# schema_mpb1_1_IO.net
KiCad netlist of a schematic drawn in EAGLE
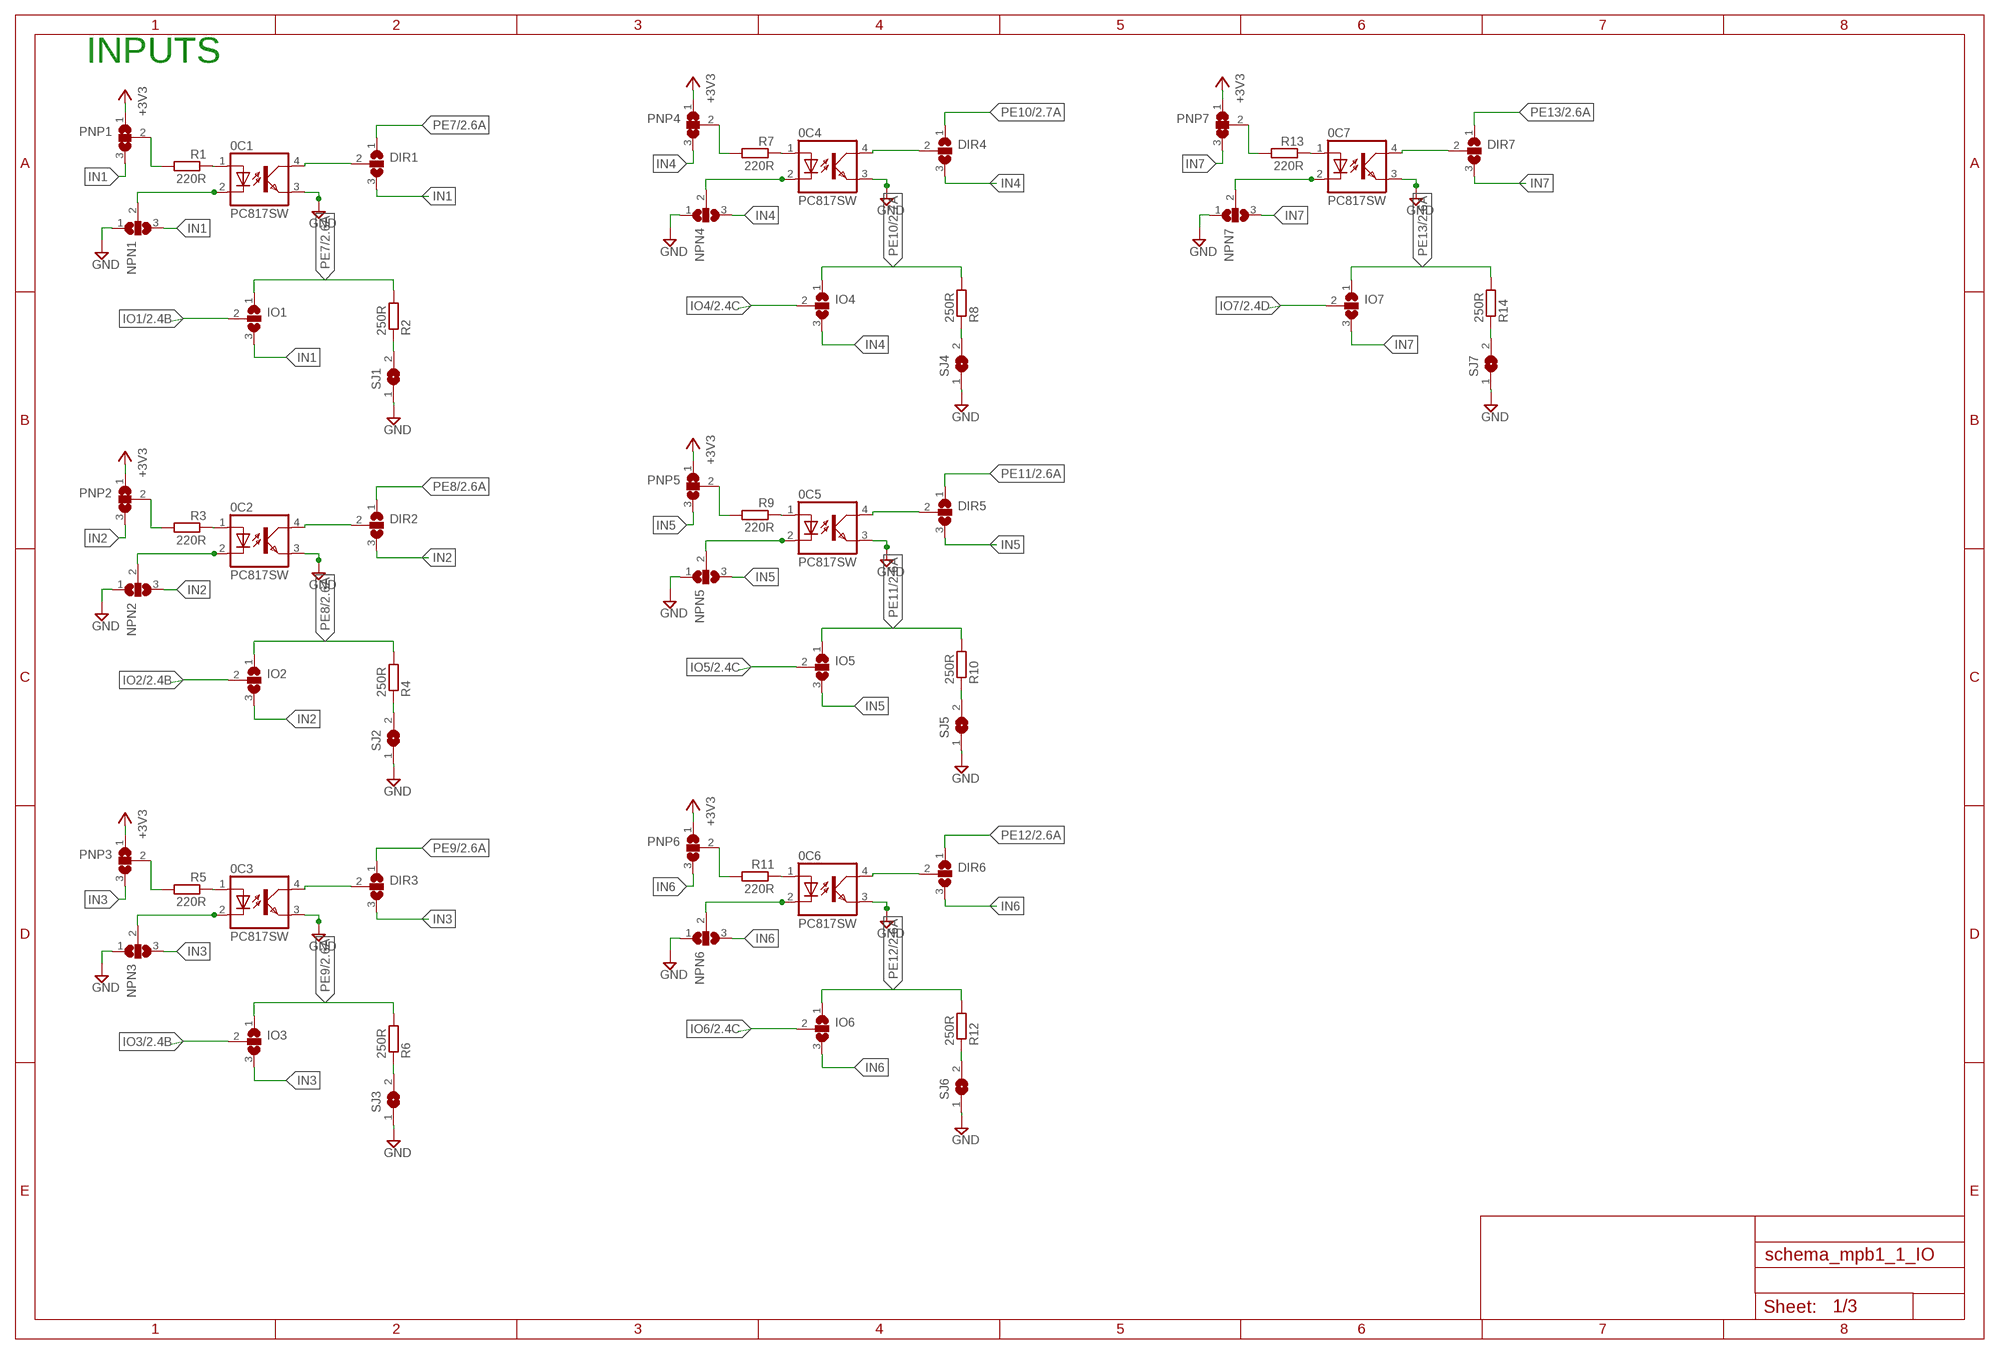
[diagram p0: schematic, sheet 1]
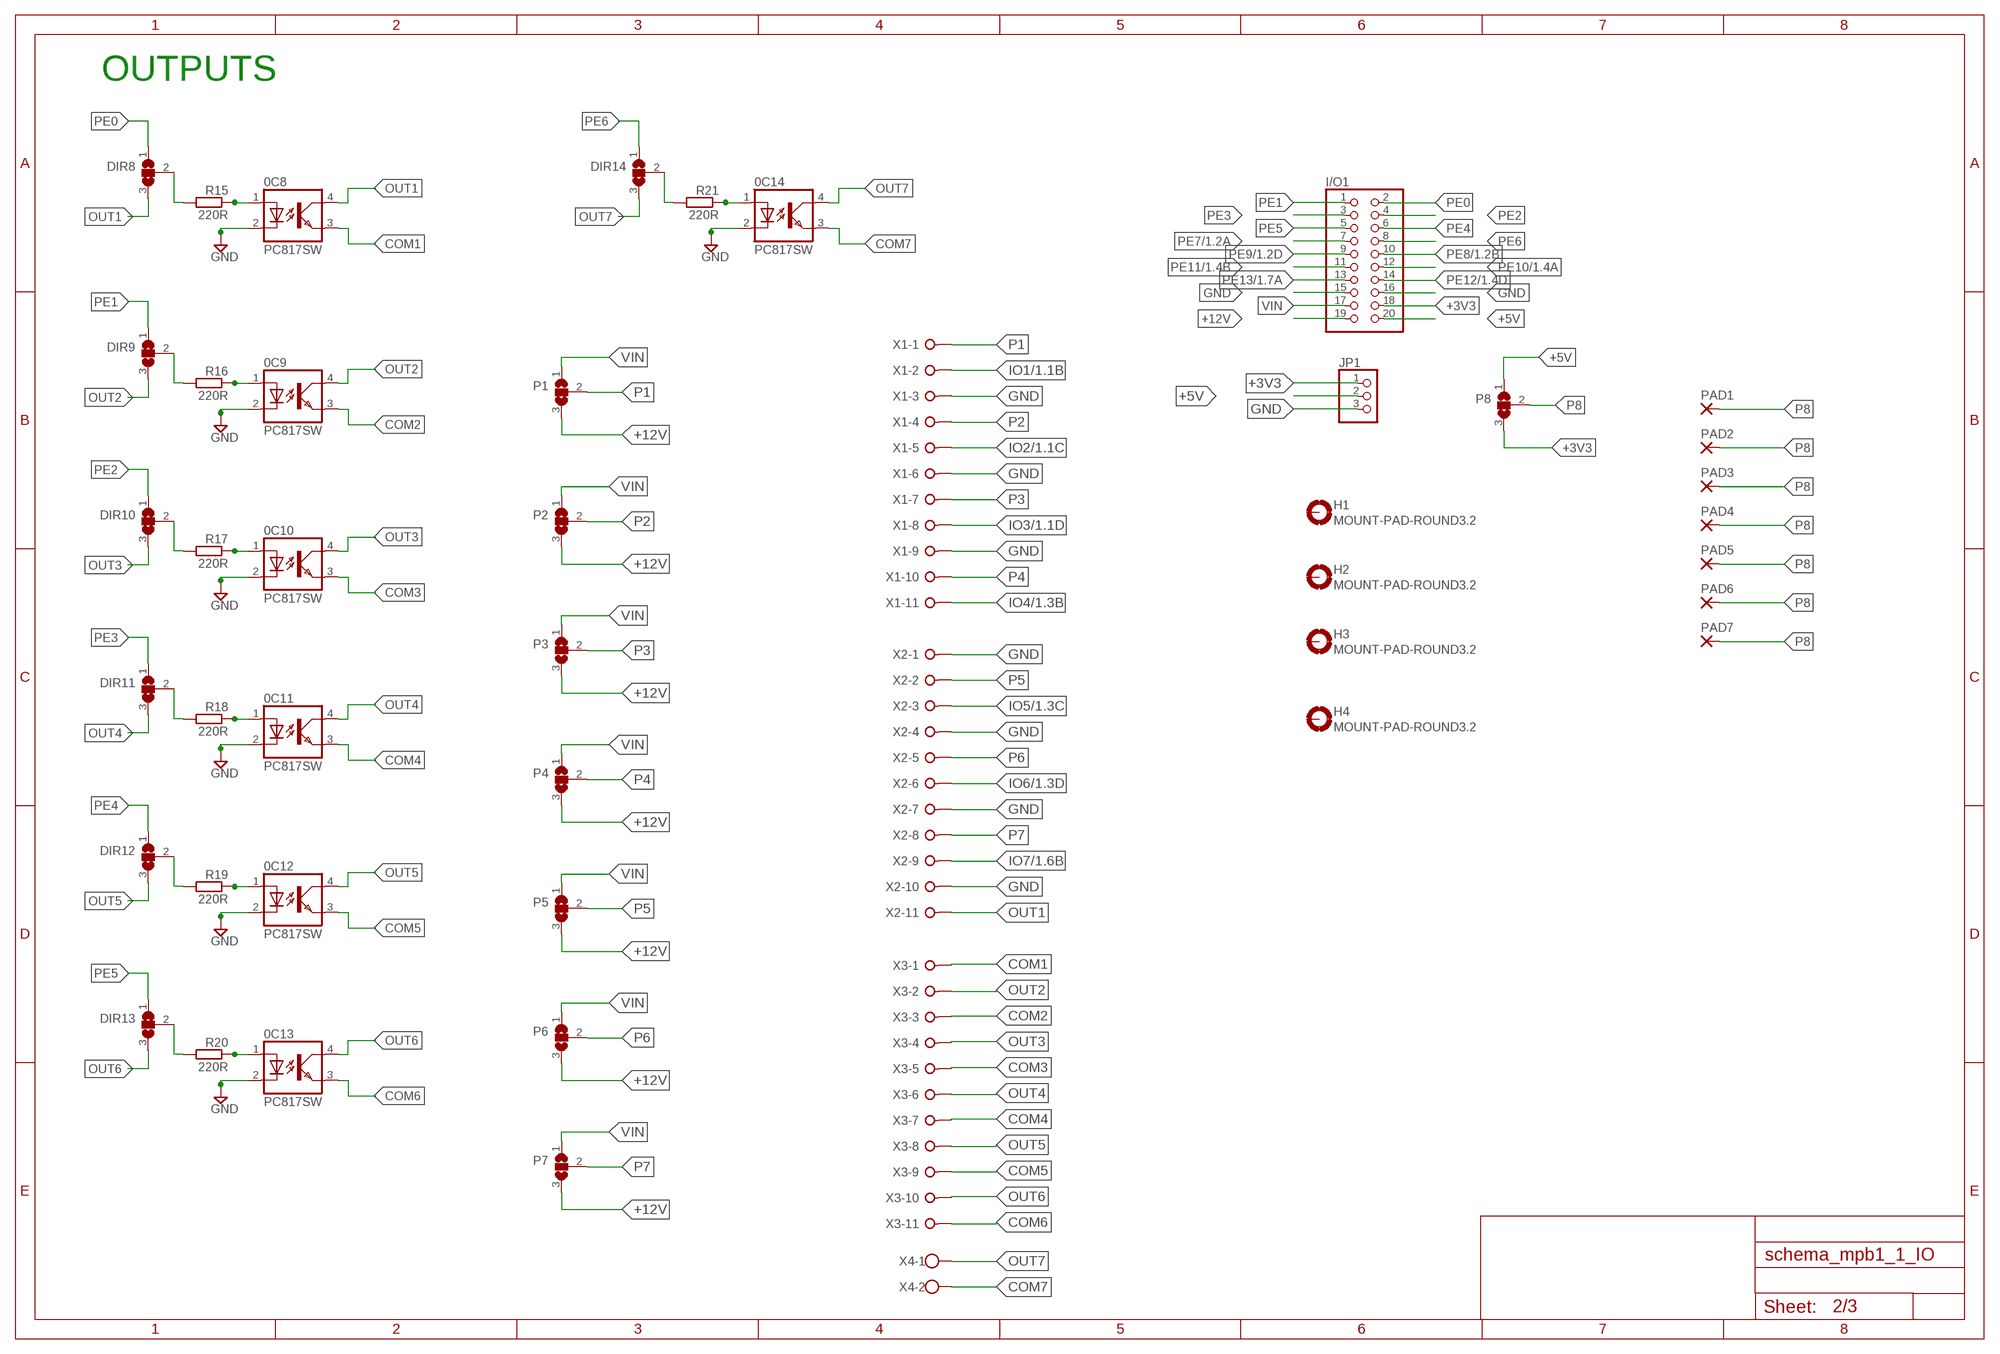
[diagram p1: schematic, sheet 2]

(export (version "E")
  (design (tool "Eeschema 10.0.6"))
  (components
    (comp (ref "0C1")
      (value "PC817SW")
      (footprint "eagle-import:PC817SMTW")
      (libsource (lib "eagle-import") (part "PC817SW"))
    )
    (comp (ref "0C2")
      (value "PC817SW")
      (footprint "eagle-import:PC817SMTW")
      (libsource (lib "eagle-import") (part "PC817SW"))
    )
    (comp (ref "0C3")
      (value "PC817SW")
      (footprint "eagle-import:PC817SMTW")
      (libsource (lib "eagle-import") (part "PC817SW"))
    )
    (comp (ref "0C4")
      (value "PC817SW")
      (footprint "eagle-import:PC817SMTW")
      (libsource (lib "eagle-import") (part "PC817SW"))
    )
    (comp (ref "0C5")
      (value "PC817SW")
      (footprint "eagle-import:PC817SMTW")
      (libsource (lib "eagle-import") (part "PC817SW"))
    )
    (comp (ref "0C6")
      (value "PC817SW")
      (footprint "eagle-import:PC817SMTW")
      (libsource (lib "eagle-import") (part "PC817SW"))
    )
    (comp (ref "0C7")
      (value "PC817SW")
      (footprint "eagle-import:PC817SMTW")
      (libsource (lib "eagle-import") (part "PC817SW"))
    )
    (comp (ref "DIR1")
      (value "SJ2W")
      (footprint "eagle-import:SJ_2")
      (libsource (lib "eagle-import") (part "SJ2W"))
    )
    (comp (ref "DIR2")
      (value "SJ2W")
      (footprint "eagle-import:SJ_2")
      (libsource (lib "eagle-import") (part "SJ2W"))
    )
    (comp (ref "DIR3")
      (value "SJ2W")
      (footprint "eagle-import:SJ_2")
      (libsource (lib "eagle-import") (part "SJ2W"))
    )
    (comp (ref "DIR4")
      (value "SJ2W")
      (footprint "eagle-import:SJ_2")
      (libsource (lib "eagle-import") (part "SJ2W"))
    )
    (comp (ref "DIR5")
      (value "SJ2W")
      (footprint "eagle-import:SJ_2")
      (libsource (lib "eagle-import") (part "SJ2W"))
    )
    (comp (ref "DIR6")
      (value "SJ2W")
      (footprint "eagle-import:SJ_2")
      (libsource (lib "eagle-import") (part "SJ2W"))
    )
    (comp (ref "DIR7")
      (value "SJ2W")
      (footprint "eagle-import:SJ_2")
      (libsource (lib "eagle-import") (part "SJ2W"))
    )
    (comp (ref "IO1")
      (value "SJ2W")
      (footprint "eagle-import:SJ_2")
      (libsource (lib "eagle-import") (part "SJ2W"))
    )
    (comp (ref "IO2")
      (value "SJ2W")
      (footprint "eagle-import:SJ_2")
      (libsource (lib "eagle-import") (part "SJ2W"))
    )
    (comp (ref "IO3")
      (value "SJ2W")
      (footprint "eagle-import:SJ_2")
      (libsource (lib "eagle-import") (part "SJ2W"))
    )
    (comp (ref "IO4")
      (value "SJ2W")
      (footprint "eagle-import:SJ_2")
      (libsource (lib "eagle-import") (part "SJ2W"))
    )
    (comp (ref "IO5")
      (value "SJ2W")
      (footprint "eagle-import:SJ_2")
      (libsource (lib "eagle-import") (part "SJ2W"))
    )
    (comp (ref "IO6")
      (value "SJ2W")
      (footprint "eagle-import:SJ_2")
      (libsource (lib "eagle-import") (part "SJ2W"))
    )
    (comp (ref "IO7")
      (value "SJ2W")
      (footprint "eagle-import:SJ_2")
      (libsource (lib "eagle-import") (part "SJ2W"))
    )
    (comp (ref "NPN1")
      (value "SJ2W")
      (footprint "eagle-import:SJ_2")
      (libsource (lib "eagle-import") (part "SJ2W"))
    )
    (comp (ref "NPN2")
      (value "SJ2W")
      (footprint "eagle-import:SJ_2")
      (libsource (lib "eagle-import") (part "SJ2W"))
    )
    (comp (ref "NPN3")
      (value "SJ2W")
      (footprint "eagle-import:SJ_2")
      (libsource (lib "eagle-import") (part "SJ2W"))
    )
    (comp (ref "NPN4")
      (value "SJ2W")
      (footprint "eagle-import:SJ_2")
      (libsource (lib "eagle-import") (part "SJ2W"))
    )
    (comp (ref "NPN5")
      (value "SJ2W")
      (footprint "eagle-import:SJ_2")
      (libsource (lib "eagle-import") (part "SJ2W"))
    )
    (comp (ref "NPN6")
      (value "SJ2W")
      (footprint "eagle-import:SJ_2")
      (libsource (lib "eagle-import") (part "SJ2W"))
    )
    (comp (ref "NPN7")
      (value "SJ2W")
      (footprint "eagle-import:SJ_2")
      (libsource (lib "eagle-import") (part "SJ2W"))
    )
    (comp (ref "PNP1")
      (value "SJ2W")
      (footprint "eagle-import:SJ_2")
      (libsource (lib "eagle-import") (part "SJ2W"))
    )
    (comp (ref "PNP2")
      (value "SJ2W")
      (footprint "eagle-import:SJ_2")
      (libsource (lib "eagle-import") (part "SJ2W"))
    )
    (comp (ref "PNP3")
      (value "SJ2W")
      (footprint "eagle-import:SJ_2")
      (libsource (lib "eagle-import") (part "SJ2W"))
    )
    (comp (ref "PNP4")
      (value "SJ2W")
      (footprint "eagle-import:SJ_2")
      (libsource (lib "eagle-import") (part "SJ2W"))
    )
    (comp (ref "PNP5")
      (value "SJ2W")
      (footprint "eagle-import:SJ_2")
      (libsource (lib "eagle-import") (part "SJ2W"))
    )
    (comp (ref "PNP6")
      (value "SJ2W")
      (footprint "eagle-import:SJ_2")
      (libsource (lib "eagle-import") (part "SJ2W"))
    )
    (comp (ref "PNP7")
      (value "SJ2W")
      (footprint "eagle-import:SJ_2")
      (libsource (lib "eagle-import") (part "SJ2W"))
    )
    (comp (ref "R1")
      (value "220R")
      (footprint "eagle-import:R0603")
      (libsource (lib "eagle-import") (part "R-EU_R0603"))
    )
    (comp (ref "R2")
      (value "250R")
      (footprint "eagle-import:R0603")
      (libsource (lib "eagle-import") (part "R-EU_R0603"))
    )
    (comp (ref "R3")
      (value "220R")
      (footprint "eagle-import:R0603")
      (libsource (lib "eagle-import") (part "R-EU_R0603"))
    )
    (comp (ref "R4")
      (value "250R")
      (footprint "eagle-import:R0603")
      (libsource (lib "eagle-import") (part "R-EU_R0603"))
    )
    (comp (ref "R5")
      (value "220R")
      (footprint "eagle-import:R0603")
      (libsource (lib "eagle-import") (part "R-EU_R0603"))
    )
    (comp (ref "R6")
      (value "250R")
      (footprint "eagle-import:R0603")
      (libsource (lib "eagle-import") (part "R-EU_R0603"))
    )
    (comp (ref "R7")
      (value "220R")
      (footprint "eagle-import:R0603")
      (libsource (lib "eagle-import") (part "R-EU_R0603"))
    )
    (comp (ref "R8")
      (value "250R")
      (footprint "eagle-import:R0603")
      (libsource (lib "eagle-import") (part "R-EU_R0603"))
    )
    (comp (ref "R9")
      (value "220R")
      (footprint "eagle-import:R0603")
      (libsource (lib "eagle-import") (part "R-EU_R0603"))
    )
    (comp (ref "R10")
      (value "250R")
      (footprint "eagle-import:R0603")
      (libsource (lib "eagle-import") (part "R-EU_R0603"))
    )
    (comp (ref "R11")
      (value "220R")
      (footprint "eagle-import:R0603")
      (libsource (lib "eagle-import") (part "R-EU_R0603"))
    )
    (comp (ref "R12")
      (value "250R")
      (footprint "eagle-import:R0603")
      (libsource (lib "eagle-import") (part "R-EU_R0603"))
    )
    (comp (ref "R13")
      (value "220R")
      (footprint "eagle-import:R0603")
      (libsource (lib "eagle-import") (part "R-EU_R0603"))
    )
    (comp (ref "R14")
      (value "250R")
      (footprint "eagle-import:R0603")
      (libsource (lib "eagle-import") (part "R-EU_R0603"))
    )
    (comp (ref "SJ1") (value "SJ") (footprint "eagle-import:SJ") (libsource (lib "eagle-import") (part "SJ")))
    (comp (ref "SJ2") (value "SJ") (footprint "eagle-import:SJ") (libsource (lib "eagle-import") (part "SJ")))
    (comp (ref "SJ3") (value "SJ") (footprint "eagle-import:SJ") (libsource (lib "eagle-import") (part "SJ")))
    (comp (ref "SJ4") (value "SJ") (footprint "eagle-import:SJ") (libsource (lib "eagle-import") (part "SJ")))
    (comp (ref "SJ5") (value "SJ") (footprint "eagle-import:SJ") (libsource (lib "eagle-import") (part "SJ")))
    (comp (ref "SJ6") (value "SJ") (footprint "eagle-import:SJ") (libsource (lib "eagle-import") (part "SJ")))
    (comp (ref "SJ7") (value "SJ") (footprint "eagle-import:SJ") (libsource (lib "eagle-import") (part "SJ")))
    (comp (ref "0C8")
      (value "PC817SW")
      (footprint "eagle-import:PC817SMTW")
      (libsource (lib "eagle-import") (part "PC817SW"))
    )
    (comp (ref "0C9")
      (value "PC817SW")
      (footprint "eagle-import:PC817SMTW")
      (libsource (lib "eagle-import") (part "PC817SW"))
    )
    (comp (ref "0C10")
      (value "PC817SW")
      (footprint "eagle-import:PC817SMTW")
      (libsource (lib "eagle-import") (part "PC817SW"))
    )
    (comp (ref "0C11")
      (value "PC817SW")
      (footprint "eagle-import:PC817SMTW")
      (libsource (lib "eagle-import") (part "PC817SW"))
    )
    (comp (ref "0C12")
      (value "PC817SW")
      (footprint "eagle-import:PC817SMTW")
      (libsource (lib "eagle-import") (part "PC817SW"))
    )
    (comp (ref "0C13")
      (value "PC817SW")
      (footprint "eagle-import:PC817SMTW")
      (libsource (lib "eagle-import") (part "PC817SW"))
    )
    (comp (ref "0C14")
      (value "PC817SW")
      (footprint "eagle-import:PC817SMTW")
      (libsource (lib "eagle-import") (part "PC817SW"))
    )
    (comp (ref "DIR8")
      (value "SJ2W")
      (footprint "eagle-import:SJ_2")
      (libsource (lib "eagle-import") (part "SJ2W"))
    )
    (comp (ref "DIR9")
      (value "SJ2W")
      (footprint "eagle-import:SJ_2")
      (libsource (lib "eagle-import") (part "SJ2W"))
    )
    (comp (ref "DIR10")
      (value "SJ2W")
      (footprint "eagle-import:SJ_2")
      (libsource (lib "eagle-import") (part "SJ2W"))
    )
    (comp (ref "DIR11")
      (value "SJ2W")
      (footprint "eagle-import:SJ_2")
      (libsource (lib "eagle-import") (part "SJ2W"))
    )
    (comp (ref "DIR12")
      (value "SJ2W")
      (footprint "eagle-import:SJ_2")
      (libsource (lib "eagle-import") (part "SJ2W"))
    )
    (comp (ref "DIR13")
      (value "SJ2W")
      (footprint "eagle-import:SJ_2")
      (libsource (lib "eagle-import") (part "SJ2W"))
    )
    (comp (ref "DIR14")
      (value "SJ2W")
      (footprint "eagle-import:SJ_2")
      (libsource (lib "eagle-import") (part "SJ2W"))
    )
    (comp (ref "H1")
      (value "MOUNT-PAD-ROUND3.2")
      (footprint "eagle-import:3,2-PAD")
      (libsource (lib "eagle-import") (part "MOUNT-PAD-ROUND3.2"))
    )
    (comp (ref "H2")
      (value "MOUNT-PAD-ROUND3.2")
      (footprint "eagle-import:3,2-PAD")
      (libsource (lib "eagle-import") (part "MOUNT-PAD-ROUND3.2"))
    )
    (comp (ref "H3")
      (value "MOUNT-PAD-ROUND3.2")
      (footprint "eagle-import:3,2-PAD")
      (libsource (lib "eagle-import") (part "MOUNT-PAD-ROUND3.2"))
    )
    (comp (ref "H4")
      (value "MOUNT-PAD-ROUND3.2")
      (footprint "eagle-import:3,2-PAD")
      (libsource (lib "eagle-import") (part "MOUNT-PAD-ROUND3.2"))
    )
    (comp (ref "I/O1")
      (value "PINHD-2X10_2.54")
      (footprint "eagle-import:2X10")
      (libsource (lib "eagle-import") (part "PINHD-2X10_2.54"))
    )
    (comp (ref "JP1")
      (value "PINHD-1X3")
      (footprint "eagle-import:1X03")
      (libsource (lib "eagle-import") (part "PINHD-1X3"))
    )
    (comp (ref "P1")
      (value "SJ2WW")
      (footprint "eagle-import:SJ_2W")
      (libsource (lib "eagle-import") (part "SJ2WW"))
    )
    (comp (ref "P2")
      (value "SJ2WW")
      (footprint "eagle-import:SJ_2W")
      (libsource (lib "eagle-import") (part "SJ2WW"))
    )
    (comp (ref "P3")
      (value "SJ2WW")
      (footprint "eagle-import:SJ_2W")
      (libsource (lib "eagle-import") (part "SJ2WW"))
    )
    (comp (ref "P4")
      (value "SJ2WW")
      (footprint "eagle-import:SJ_2W")
      (libsource (lib "eagle-import") (part "SJ2WW"))
    )
    (comp (ref "P5")
      (value "SJ2WW")
      (footprint "eagle-import:SJ_2W")
      (libsource (lib "eagle-import") (part "SJ2WW"))
    )
    (comp (ref "P6")
      (value "SJ2WW")
      (footprint "eagle-import:SJ_2W")
      (libsource (lib "eagle-import") (part "SJ2WW"))
    )
    (comp (ref "P7")
      (value "SJ2WW")
      (footprint "eagle-import:SJ_2W")
      (libsource (lib "eagle-import") (part "SJ2WW"))
    )
    (comp (ref "P8")
      (value "SJ2WW")
      (footprint "eagle-import:SJ_2W")
      (libsource (lib "eagle-import") (part "SJ2WW"))
    )
    (comp (ref "PAD1")
      (value "SMD2")
      (footprint "eagle-import:SMD1,27-2,54")
      (libsource (lib "eagle-import") (part "SMD2"))
    )
    (comp (ref "PAD2")
      (value "SMD2")
      (footprint "eagle-import:SMD1,27-2,54")
      (libsource (lib "eagle-import") (part "SMD2"))
    )
    (comp (ref "PAD3")
      (value "SMD2")
      (footprint "eagle-import:SMD1,27-2,54")
      (libsource (lib "eagle-import") (part "SMD2"))
    )
    (comp (ref "PAD4")
      (value "SMD2")
      (footprint "eagle-import:SMD1,27-2,54")
      (libsource (lib "eagle-import") (part "SMD2"))
    )
    (comp (ref "PAD5")
      (value "SMD2")
      (footprint "eagle-import:SMD1,27-2,54")
      (libsource (lib "eagle-import") (part "SMD2"))
    )
    (comp (ref "PAD6")
      (value "SMD2")
      (footprint "eagle-import:SMD1,27-2,54")
      (libsource (lib "eagle-import") (part "SMD2"))
    )
    (comp (ref "PAD7")
      (value "SMD2")
      (footprint "eagle-import:SMD1,27-2,54")
      (libsource (lib "eagle-import") (part "SMD2"))
    )
    (comp (ref "R15")
      (value "220R")
      (footprint "eagle-import:R0603")
      (libsource (lib "eagle-import") (part "R-EU_R0603"))
    )
    (comp (ref "R16")
      (value "220R")
      (footprint "eagle-import:R0603")
      (libsource (lib "eagle-import") (part "R-EU_R0603"))
    )
    (comp (ref "R17")
      (value "220R")
      (footprint "eagle-import:R0603")
      (libsource (lib "eagle-import") (part "R-EU_R0603"))
    )
    (comp (ref "R18")
      (value "220R")
      (footprint "eagle-import:R0603")
      (libsource (lib "eagle-import") (part "R-EU_R0603"))
    )
    (comp (ref "R19")
      (value "220R")
      (footprint "eagle-import:R0603")
      (libsource (lib "eagle-import") (part "R-EU_R0603"))
    )
    (comp (ref "R20")
      (value "220R")
      (footprint "eagle-import:R0603")
      (libsource (lib "eagle-import") (part "R-EU_R0603"))
    )
    (comp (ref "R21")
      (value "220R")
      (footprint "eagle-import:R0603")
      (libsource (lib "eagle-import") (part "R-EU_R0603"))
    )
    (comp (ref "X1")
      (value "W237-11P")
      (footprint "eagle-import:W237-11P")
      (libsource (lib "eagle-import") (part "W237-11P"))
    )
    (comp (ref "X2")
      (value "W237-11P")
      (footprint "eagle-import:W237-11P")
      (libsource (lib "eagle-import") (part "W237-11P"))
    )
    (comp (ref "X3")
      (value "W237-11P")
      (footprint "eagle-import:W237-11P")
      (libsource (lib "eagle-import") (part "W237-11P"))
    )
    (comp (ref "X4")
      (value "W237-102")
      (footprint "eagle-import:W237-102")
      (fields (field (name "MPN") "237-102"))
      (libsource (lib "eagle-import") (part "W237-102"))
    )
  )
  (nets
    (net (code "1") (name "+3V3") (class "Default")
      (node (ref "I/O1") (pin "18") (pinfunction "18_18") (pintype "passive"))
      (node (ref "JP1") (pin "1") (pinfunction "1_1") (pintype "passive"))
      (node (ref "P8") (pin "3") (pinfunction "3_3") (pintype "passive"))
      (node (ref "PNP1") (pin "1") (pinfunction "1_1") (pintype "passive"))
      (node (ref "PNP2") (pin "1") (pinfunction "1_1") (pintype "passive"))
      (node (ref "PNP3") (pin "1") (pinfunction "1_1") (pintype "passive"))
      (node (ref "PNP4") (pin "1") (pinfunction "1_1") (pintype "passive"))
      (node (ref "PNP5") (pin "1") (pinfunction "1_1") (pintype "passive"))
      (node (ref "PNP6") (pin "1") (pinfunction "1_1") (pintype "passive"))
      (node (ref "PNP7") (pin "1") (pinfunction "1_1") (pintype "passive"))
    )
    (net (code "2") (name "+5V") (class "Default")
      (node (ref "I/O1") (pin "20") (pinfunction "20_20") (pintype "passive"))
      (node (ref "JP1") (pin "2") (pinfunction "2_2") (pintype "passive"))
      (node (ref "P8") (pin "1") (pinfunction "1_1") (pintype "passive"))
    )
    (net (code "3") (name "+12V") (class "Default")
      (node (ref "I/O1") (pin "19") (pinfunction "19_19") (pintype "passive"))
      (node (ref "P1") (pin "3") (pinfunction "3_3") (pintype "passive"))
      (node (ref "P2") (pin "3") (pinfunction "3_3") (pintype "passive"))
      (node (ref "P3") (pin "3") (pinfunction "3_3") (pintype "passive"))
      (node (ref "P4") (pin "3") (pinfunction "3_3") (pintype "passive"))
      (node (ref "P5") (pin "3") (pinfunction "3_3") (pintype "passive"))
      (node (ref "P6") (pin "3") (pinfunction "3_3") (pintype "passive"))
      (node (ref "P7") (pin "3") (pinfunction "3_3") (pintype "passive"))
    )
    (net (code "4") (name "COM1") (class "Default")
      (node (ref "0C8") (pin "3") (pinfunction "EMIT_3") (pintype "passive"))
      (node (ref "X3") (pin "1") (pinfunction "KL_1") (pintype "passive"))
    )
    (net (code "5") (name "COM2") (class "Default")
      (node (ref "0C9") (pin "3") (pinfunction "EMIT_3") (pintype "passive"))
      (node (ref "X3") (pin "3") (pinfunction "KL_3") (pintype "passive"))
    )
    (net (code "6") (name "COM3") (class "Default")
      (node (ref "0C10") (pin "3") (pinfunction "EMIT_3") (pintype "passive"))
      (node (ref "X3") (pin "5") (pinfunction "KL_5") (pintype "passive"))
    )
    (net (code "7") (name "COM4") (class "Default")
      (node (ref "0C11") (pin "3") (pinfunction "EMIT_3") (pintype "passive"))
      (node (ref "X3") (pin "7") (pinfunction "KL_7") (pintype "passive"))
    )
    (net (code "8") (name "COM5") (class "Default")
      (node (ref "0C12") (pin "3") (pinfunction "EMIT_3") (pintype "passive"))
      (node (ref "X3") (pin "9") (pinfunction "KL_9") (pintype "passive"))
    )
    (net (code "9") (name "COM6") (class "Default")
      (node (ref "0C13") (pin "3") (pinfunction "EMIT_3") (pintype "passive"))
      (node (ref "X3") (pin "11") (pinfunction "KL_11") (pintype "passive"))
    )
    (net (code "10") (name "COM7") (class "Default")
      (node (ref "0C14") (pin "3") (pinfunction "EMIT_3") (pintype "passive"))
      (node (ref "X4") (pin "2") (pinfunction "KL_2") (pintype "passive"))
    )
    (net (code "11") (name "GND") (class "Default")
      (node (ref "0C1") (pin "3") (pinfunction "EMIT_3") (pintype "passive"))
      (node (ref "0C10") (pin "2") (pinfunction "C_2") (pintype "passive"))
      (node (ref "0C11") (pin "2") (pinfunction "C_2") (pintype "passive"))
      (node (ref "0C12") (pin "2") (pinfunction "C_2") (pintype "passive"))
      (node (ref "0C13") (pin "2") (pinfunction "C_2") (pintype "passive"))
      (node (ref "0C14") (pin "2") (pinfunction "C_2") (pintype "passive"))
      (node (ref "0C2") (pin "3") (pinfunction "EMIT_3") (pintype "passive"))
      (node (ref "0C3") (pin "3") (pinfunction "EMIT_3") (pintype "passive"))
      (node (ref "0C4") (pin "3") (pinfunction "EMIT_3") (pintype "passive"))
      (node (ref "0C5") (pin "3") (pinfunction "EMIT_3") (pintype "passive"))
      (node (ref "0C6") (pin "3") (pinfunction "EMIT_3") (pintype "passive"))
      (node (ref "0C7") (pin "3") (pinfunction "EMIT_3") (pintype "passive"))
      (node (ref "0C8") (pin "2") (pinfunction "C_2") (pintype "passive"))
      (node (ref "0C9") (pin "2") (pinfunction "C_2") (pintype "passive"))
      (node (ref "I/O1") (pin "15") (pinfunction "15_15") (pintype "passive"))
      (node (ref "I/O1") (pin "16") (pinfunction "16_16") (pintype "passive"))
      (node (ref "JP1") (pin "3") (pinfunction "3_3") (pintype "passive"))
      (node (ref "NPN1") (pin "1") (pinfunction "1_1") (pintype "passive"))
      (node (ref "NPN2") (pin "1") (pinfunction "1_1") (pintype "passive"))
      (node (ref "NPN3") (pin "1") (pinfunction "1_1") (pintype "passive"))
      (node (ref "NPN4") (pin "1") (pinfunction "1_1") (pintype "passive"))
      (node (ref "NPN5") (pin "1") (pinfunction "1_1") (pintype "passive"))
      (node (ref "NPN6") (pin "1") (pinfunction "1_1") (pintype "passive"))
      (node (ref "NPN7") (pin "1") (pinfunction "1_1") (pintype "passive"))
      (node (ref "SJ1") (pin "1") (pinfunction "1_1") (pintype "passive"))
      (node (ref "SJ2") (pin "1") (pinfunction "1_1") (pintype "passive"))
      (node (ref "SJ3") (pin "1") (pinfunction "1_1") (pintype "passive"))
      (node (ref "SJ4") (pin "1") (pinfunction "1_1") (pintype "passive"))
      (node (ref "SJ5") (pin "1") (pinfunction "1_1") (pintype "passive"))
      (node (ref "SJ6") (pin "1") (pinfunction "1_1") (pintype "passive"))
      (node (ref "SJ7") (pin "1") (pinfunction "1_1") (pintype "passive"))
      (node (ref "X1") (pin "3") (pinfunction "KL_3") (pintype "passive"))
      (node (ref "X1") (pin "6") (pinfunction "KL_6") (pintype "passive"))
      (node (ref "X1") (pin "9") (pinfunction "KL_9") (pintype "passive"))
      (node (ref "X2") (pin "1") (pinfunction "KL_1") (pintype "passive"))
      (node (ref "X2") (pin "10") (pinfunction "KL_10") (pintype "passive"))
      (node (ref "X2") (pin "4") (pinfunction "KL_4") (pintype "passive"))
      (node (ref "X2") (pin "7") (pinfunction "KL_7") (pintype "passive"))
    )
    (net (code "12") (name "IN1") (class "Default")
      (node (ref "DIR1") (pin "3") (pinfunction "3_3") (pintype "passive"))
      (node (ref "IO1") (pin "3") (pinfunction "3_3") (pintype "passive"))
      (node (ref "NPN1") (pin "3") (pinfunction "3_3") (pintype "passive"))
      (node (ref "PNP1") (pin "3") (pinfunction "3_3") (pintype "passive"))
    )
    (net (code "13") (name "IN2") (class "Default")
      (node (ref "DIR2") (pin "3") (pinfunction "3_3") (pintype "passive"))
      (node (ref "IO2") (pin "3") (pinfunction "3_3") (pintype "passive"))
      (node (ref "NPN2") (pin "3") (pinfunction "3_3") (pintype "passive"))
      (node (ref "PNP2") (pin "3") (pinfunction "3_3") (pintype "passive"))
    )
    (net (code "14") (name "IN3") (class "Default")
      (node (ref "DIR3") (pin "3") (pinfunction "3_3") (pintype "passive"))
      (node (ref "IO3") (pin "3") (pinfunction "3_3") (pintype "passive"))
      (node (ref "NPN3") (pin "3") (pinfunction "3_3") (pintype "passive"))
      (node (ref "PNP3") (pin "3") (pinfunction "3_3") (pintype "passive"))
    )
    (net (code "15") (name "IN4") (class "Default")
      (node (ref "DIR4") (pin "3") (pinfunction "3_3") (pintype "passive"))
      (node (ref "IO4") (pin "3") (pinfunction "3_3") (pintype "passive"))
      (node (ref "NPN4") (pin "3") (pinfunction "3_3") (pintype "passive"))
      (node (ref "PNP4") (pin "3") (pinfunction "3_3") (pintype "passive"))
    )
    (net (code "16") (name "IN5") (class "Default")
      (node (ref "DIR5") (pin "3") (pinfunction "3_3") (pintype "passive"))
      (node (ref "IO5") (pin "3") (pinfunction "3_3") (pintype "passive"))
      (node (ref "NPN5") (pin "3") (pinfunction "3_3") (pintype "passive"))
      (node (ref "PNP5") (pin "3") (pinfunction "3_3") (pintype "passive"))
    )
    (net (code "17") (name "IN6") (class "Default")
      (node (ref "DIR6") (pin "3") (pinfunction "3_3") (pintype "passive"))
      (node (ref "IO6") (pin "3") (pinfunction "3_3") (pintype "passive"))
      (node (ref "NPN6") (pin "3") (pinfunction "3_3") (pintype "passive"))
      (node (ref "PNP6") (pin "3") (pinfunction "3_3") (pintype "passive"))
    )
    (net (code "18") (name "IN7") (class "Default")
      (node (ref "DIR7") (pin "3") (pinfunction "3_3") (pintype "passive"))
      (node (ref "IO7") (pin "3") (pinfunction "3_3") (pintype "passive"))
      (node (ref "NPN7") (pin "3") (pinfunction "3_3") (pintype "passive"))
      (node (ref "PNP7") (pin "3") (pinfunction "3_3") (pintype "passive"))
    )
    (net (code "19") (name "IO1") (class "Default")
      (node (ref "IO1") (pin "2") (pinfunction "2_2") (pintype "passive"))
      (node (ref "X1") (pin "2") (pinfunction "KL_2") (pintype "passive"))
    )
    (net (code "20") (name "IO2") (class "Default")
      (node (ref "IO2") (pin "2") (pinfunction "2_2") (pintype "passive"))
      (node (ref "X1") (pin "5") (pinfunction "KL_5") (pintype "passive"))
    )
    (net (code "21") (name "IO3") (class "Default")
      (node (ref "IO3") (pin "2") (pinfunction "2_2") (pintype "passive"))
      (node (ref "X1") (pin "8") (pinfunction "KL_8") (pintype "passive"))
    )
    (net (code "22") (name "IO4") (class "Default")
      (node (ref "IO4") (pin "2") (pinfunction "2_2") (pintype "passive"))
      (node (ref "X1") (pin "11") (pinfunction "KL_11") (pintype "passive"))
    )
    (net (code "23") (name "IO5") (class "Default")
      (node (ref "IO5") (pin "2") (pinfunction "2_2") (pintype "passive"))
      (node (ref "X2") (pin "3") (pinfunction "KL_3") (pintype "passive"))
    )
    (net (code "24") (name "IO6") (class "Default")
      (node (ref "IO6") (pin "2") (pinfunction "2_2") (pintype "passive"))
      (node (ref "X2") (pin "6") (pinfunction "KL_6") (pintype "passive"))
    )
    (net (code "25") (name "IO7") (class "Default")
      (node (ref "IO7") (pin "2") (pinfunction "2_2") (pintype "passive"))
      (node (ref "X2") (pin "9") (pinfunction "KL_9") (pintype "passive"))
    )
    (net (code "26") (name "Net-(0C1-A)") (class "Default")
      (node (ref "0C1") (pin "1") (pinfunction "A_1") (pintype "passive"))
      (node (ref "R1") (pin "1") (pinfunction "1_1") (pintype "passive"))
    )
    (net (code "27") (name "Net-(0C1-C)") (class "Default")
      (node (ref "0C1") (pin "2") (pinfunction "C_2") (pintype "passive"))
      (node (ref "NPN1") (pin "2") (pinfunction "2_2") (pintype "passive"))
    )
    (net (code "28") (name "Net-(0C1-COL)") (class "Default")
      (node (ref "0C1") (pin "4") (pinfunction "COL_4") (pintype "passive"))
      (node (ref "DIR1") (pin "2") (pinfunction "2_2") (pintype "passive"))
    )
    (net (code "29") (name "Net-(0C2-A)") (class "Default")
      (node (ref "0C2") (pin "1") (pinfunction "A_1") (pintype "passive"))
      (node (ref "R3") (pin "1") (pinfunction "1_1") (pintype "passive"))
    )
    (net (code "30") (name "Net-(0C2-C)") (class "Default")
      (node (ref "0C2") (pin "2") (pinfunction "C_2") (pintype "passive"))
      (node (ref "NPN2") (pin "2") (pinfunction "2_2") (pintype "passive"))
    )
    (net (code "31") (name "Net-(0C2-COL)") (class "Default")
      (node (ref "0C2") (pin "4") (pinfunction "COL_4") (pintype "passive"))
      (node (ref "DIR2") (pin "2") (pinfunction "2_2") (pintype "passive"))
    )
    (net (code "32") (name "Net-(0C3-A)") (class "Default")
      (node (ref "0C3") (pin "1") (pinfunction "A_1") (pintype "passive"))
      (node (ref "R5") (pin "1") (pinfunction "1_1") (pintype "passive"))
    )
    (net (code "33") (name "Net-(0C3-C)") (class "Default")
      (node (ref "0C3") (pin "2") (pinfunction "C_2") (pintype "passive"))
      (node (ref "NPN3") (pin "2") (pinfunction "2_2") (pintype "passive"))
    )
    (net (code "34") (name "Net-(0C3-COL)") (class "Default")
      (node (ref "0C3") (pin "4") (pinfunction "COL_4") (pintype "passive"))
      (node (ref "DIR3") (pin "2") (pinfunction "2_2") (pintype "passive"))
    )
    (net (code "35") (name "Net-(0C4-A)") (class "Default")
      (node (ref "0C4") (pin "1") (pinfunction "A_1") (pintype "passive"))
      (node (ref "R7") (pin "1") (pinfunction "1_1") (pintype "passive"))
    )
    (net (code "36") (name "Net-(0C4-C)") (class "Default")
      (node (ref "0C4") (pin "2") (pinfunction "C_2") (pintype "passive"))
      (node (ref "NPN4") (pin "2") (pinfunction "2_2") (pintype "passive"))
    )
    (net (code "37") (name "Net-(0C4-COL)") (class "Default")
      (node (ref "0C4") (pin "4") (pinfunction "COL_4") (pintype "passive"))
      (node (ref "DIR4") (pin "2") (pinfunction "2_2") (pintype "passive"))
    )
    (net (code "38") (name "Net-(0C5-A)") (class "Default")
      (node (ref "0C5") (pin "1") (pinfunction "A_1") (pintype "passive"))
      (node (ref "R9") (pin "1") (pinfunction "1_1") (pintype "passive"))
    )
    (net (code "39") (name "Net-(0C5-C)") (class "Default")
      (node (ref "0C5") (pin "2") (pinfunction "C_2") (pintype "passive"))
      (node (ref "NPN5") (pin "2") (pinfunction "2_2") (pintype "passive"))
    )
    (net (code "40") (name "Net-(0C5-COL)") (class "Default")
      (node (ref "0C5") (pin "4") (pinfunction "COL_4") (pintype "passive"))
      (node (ref "DIR5") (pin "2") (pinfunction "2_2") (pintype "passive"))
    )
    (net (code "41") (name "Net-(0C6-A)") (class "Default")
      (node (ref "0C6") (pin "1") (pinfunction "A_1") (pintype "passive"))
      (node (ref "R11") (pin "1") (pinfunction "1_1") (pintype "passive"))
    )
    (net (code "42") (name "Net-(0C6-C)") (class "Default")
      (node (ref "0C6") (pin "2") (pinfunction "C_2") (pintype "passive"))
      (node (ref "NPN6") (pin "2") (pinfunction "2_2") (pintype "passive"))
    )
    (net (code "43") (name "Net-(0C6-COL)") (class "Default")
      (node (ref "0C6") (pin "4") (pinfunction "COL_4") (pintype "passive"))
      (node (ref "DIR6") (pin "2") (pinfunction "2_2") (pintype "passive"))
    )
    (net (code "44") (name "Net-(0C7-A)") (class "Default")
      (node (ref "0C7") (pin "1") (pinfunction "A_1") (pintype "passive"))
      (node (ref "R13") (pin "1") (pinfunction "1_1") (pintype "passive"))
    )
    (net (code "45") (name "Net-(0C7-C)") (class "Default")
      (node (ref "0C7") (pin "2") (pinfunction "C_2") (pintype "passive"))
      (node (ref "NPN7") (pin "2") (pinfunction "2_2") (pintype "passive"))
    )
    (net (code "46") (name "Net-(0C7-COL)") (class "Default")
      (node (ref "0C7") (pin "4") (pinfunction "COL_4") (pintype "passive"))
      (node (ref "DIR7") (pin "2") (pinfunction "2_2") (pintype "passive"))
    )
    (net (code "47") (name "Net-(0C8-A)") (class "Default")
      (node (ref "0C8") (pin "1") (pinfunction "A_1") (pintype "passive"))
      (node (ref "R15") (pin "1") (pinfunction "1_1") (pintype "passive"))
    )
    (net (code "48") (name "Net-(0C9-A)") (class "Default")
      (node (ref "0C9") (pin "1") (pinfunction "A_1") (pintype "passive"))
      (node (ref "R16") (pin "1") (pinfunction "1_1") (pintype "passive"))
    )
    (net (code "49") (name "Net-(0C10-A)") (class "Default")
      (node (ref "0C10") (pin "1") (pinfunction "A_1") (pintype "passive"))
      (node (ref "R17") (pin "1") (pinfunction "1_1") (pintype "passive"))
    )
    (net (code "50") (name "Net-(0C11-A)") (class "Default")
      (node (ref "0C11") (pin "1") (pinfunction "A_1") (pintype "passive"))
      (node (ref "R18") (pin "1") (pinfunction "1_1") (pintype "passive"))
    )
    (net (code "51") (name "Net-(0C12-A)") (class "Default")
      (node (ref "0C12") (pin "1") (pinfunction "A_1") (pintype "passive"))
      (node (ref "R19") (pin "1") (pinfunction "1_1") (pintype "passive"))
    )
    (net (code "52") (name "Net-(0C13-A)") (class "Default")
      (node (ref "0C13") (pin "1") (pinfunction "A_1") (pintype "passive"))
      (node (ref "R20") (pin "1") (pinfunction "1_1") (pintype "passive"))
    )
    (net (code "53") (name "Net-(0C14-A)") (class "Default")
      (node (ref "0C14") (pin "1") (pinfunction "A_1") (pintype "passive"))
      (node (ref "R21") (pin "1") (pinfunction "1_1") (pintype "passive"))
    )
    (net (code "54") (name "Net-(DIR8-Pad2)") (class "Default")
      (node (ref "DIR8") (pin "2") (pinfunction "2_2") (pintype "passive"))
      (node (ref "R15") (pin "2") (pinfunction "2_2") (pintype "passive"))
    )
    (net (code "55") (name "Net-(DIR9-Pad2)") (class "Default")
      (node (ref "DIR9") (pin "2") (pinfunction "2_2") (pintype "passive"))
      (node (ref "R16") (pin "2") (pinfunction "2_2") (pintype "passive"))
    )
    (net (code "56") (name "Net-(DIR10-Pad2)") (class "Default")
      (node (ref "DIR10") (pin "2") (pinfunction "2_2") (pintype "passive"))
      (node (ref "R17") (pin "2") (pinfunction "2_2") (pintype "passive"))
    )
    (net (code "57") (name "Net-(DIR11-Pad2)") (class "Default")
      (node (ref "DIR11") (pin "2") (pinfunction "2_2") (pintype "passive"))
      (node (ref "R18") (pin "2") (pinfunction "2_2") (pintype "passive"))
    )
    (net (code "58") (name "Net-(DIR12-Pad2)") (class "Default")
      (node (ref "DIR12") (pin "2") (pinfunction "2_2") (pintype "passive"))
      (node (ref "R19") (pin "2") (pinfunction "2_2") (pintype "passive"))
    )
    (net (code "59") (name "Net-(DIR13-Pad2)") (class "Default")
      (node (ref "DIR13") (pin "2") (pinfunction "2_2") (pintype "passive"))
      (node (ref "R20") (pin "2") (pinfunction "2_2") (pintype "passive"))
    )
    (net (code "60") (name "Net-(DIR14-Pad2)") (class "Default")
      (node (ref "DIR14") (pin "2") (pinfunction "2_2") (pintype "passive"))
      (node (ref "R21") (pin "2") (pinfunction "2_2") (pintype "passive"))
    )
    (net (code "61") (name "Net-(PNP1-Pad2)") (class "Default")
      (node (ref "PNP1") (pin "2") (pinfunction "2_2") (pintype "passive"))
      (node (ref "R1") (pin "2") (pinfunction "2_2") (pintype "passive"))
    )
    (net (code "62") (name "Net-(PNP2-Pad2)") (class "Default")
      (node (ref "PNP2") (pin "2") (pinfunction "2_2") (pintype "passive"))
      (node (ref "R3") (pin "2") (pinfunction "2_2") (pintype "passive"))
    )
    (net (code "63") (name "Net-(PNP3-Pad2)") (class "Default")
      (node (ref "PNP3") (pin "2") (pinfunction "2_2") (pintype "passive"))
      (node (ref "R5") (pin "2") (pinfunction "2_2") (pintype "passive"))
    )
    (net (code "64") (name "Net-(PNP4-Pad2)") (class "Default")
      (node (ref "PNP4") (pin "2") (pinfunction "2_2") (pintype "passive"))
      (node (ref "R7") (pin "2") (pinfunction "2_2") (pintype "passive"))
    )
    (net (code "65") (name "Net-(PNP5-Pad2)") (class "Default")
      (node (ref "PNP5") (pin "2") (pinfunction "2_2") (pintype "passive"))
      (node (ref "R9") (pin "2") (pinfunction "2_2") (pintype "passive"))
    )
    (net (code "66") (name "Net-(PNP6-Pad2)") (class "Default")
      (node (ref "PNP6") (pin "2") (pinfunction "2_2") (pintype "passive"))
      (node (ref "R11") (pin "2") (pinfunction "2_2") (pintype "passive"))
    )
    (net (code "67") (name "Net-(PNP7-Pad2)") (class "Default")
      (node (ref "PNP7") (pin "2") (pinfunction "2_2") (pintype "passive"))
      (node (ref "R13") (pin "2") (pinfunction "2_2") (pintype "passive"))
    )
    (net (code "68") (name "Net-(R2-Pad1)") (class "Default")
      (node (ref "R2") (pin "1") (pinfunction "1_1") (pintype "passive"))
      (node (ref "SJ1") (pin "2") (pinfunction "2_2") (pintype "passive"))
    )
    (net (code "69") (name "Net-(R4-Pad1)") (class "Default")
      (node (ref "R4") (pin "1") (pinfunction "1_1") (pintype "passive"))
      (node (ref "SJ2") (pin "2") (pinfunction "2_2") (pintype "passive"))
    )
    (net (code "70") (name "Net-(R6-Pad1)") (class "Default")
      (node (ref "R6") (pin "1") (pinfunction "1_1") (pintype "passive"))
      (node (ref "SJ3") (pin "2") (pinfunction "2_2") (pintype "passive"))
    )
    (net (code "71") (name "Net-(R8-Pad1)") (class "Default")
      (node (ref "R8") (pin "1") (pinfunction "1_1") (pintype "passive"))
      (node (ref "SJ4") (pin "2") (pinfunction "2_2") (pintype "passive"))
    )
    (net (code "72") (name "Net-(R10-Pad1)") (class "Default")
      (node (ref "R10") (pin "1") (pinfunction "1_1") (pintype "passive"))
      (node (ref "SJ5") (pin "2") (pinfunction "2_2") (pintype "passive"))
    )
    (net (code "73") (name "Net-(R12-Pad1)") (class "Default")
      (node (ref "R12") (pin "1") (pinfunction "1_1") (pintype "passive"))
      (node (ref "SJ6") (pin "2") (pinfunction "2_2") (pintype "passive"))
    )
    (net (code "74") (name "Net-(R14-Pad1)") (class "Default")
      (node (ref "R14") (pin "1") (pinfunction "1_1") (pintype "passive"))
      (node (ref "SJ7") (pin "2") (pinfunction "2_2") (pintype "passive"))
    )
    (net (code "75") (name "OUT1") (class "Default")
      (node (ref "0C8") (pin "4") (pinfunction "COL_4") (pintype "passive"))
      (node (ref "DIR8") (pin "3") (pinfunction "3_3") (pintype "passive"))
      (node (ref "X2") (pin "11") (pinfunction "KL_11") (pintype "passive"))
    )
    (net (code "76") (name "OUT2") (class "Default")
      (node (ref "0C9") (pin "4") (pinfunction "COL_4") (pintype "passive"))
      (node (ref "DIR9") (pin "3") (pinfunction "3_3") (pintype "passive"))
      (node (ref "X3") (pin "2") (pinfunction "KL_2") (pintype "passive"))
    )
    (net (code "77") (name "OUT3") (class "Default")
      (node (ref "0C10") (pin "4") (pinfunction "COL_4") (pintype "passive"))
      (node (ref "DIR10") (pin "3") (pinfunction "3_3") (pintype "passive"))
      (node (ref "X3") (pin "4") (pinfunction "KL_4") (pintype "passive"))
    )
    (net (code "78") (name "OUT4") (class "Default")
      (node (ref "0C11") (pin "4") (pinfunction "COL_4") (pintype "passive"))
      (node (ref "DIR11") (pin "3") (pinfunction "3_3") (pintype "passive"))
      (node (ref "X3") (pin "6") (pinfunction "KL_6") (pintype "passive"))
    )
    (net (code "79") (name "OUT5") (class "Default")
      (node (ref "0C12") (pin "4") (pinfunction "COL_4") (pintype "passive"))
      (node (ref "DIR12") (pin "3") (pinfunction "3_3") (pintype "passive"))
      (node (ref "X3") (pin "8") (pinfunction "KL_8") (pintype "passive"))
    )
    (net (code "80") (name "OUT6") (class "Default")
      (node (ref "0C13") (pin "4") (pinfunction "COL_4") (pintype "passive"))
      (node (ref "DIR13") (pin "3") (pinfunction "3_3") (pintype "passive"))
      (node (ref "X3") (pin "10") (pinfunction "KL_10") (pintype "passive"))
    )
    (net (code "81") (name "OUT7") (class "Default")
      (node (ref "0C14") (pin "4") (pinfunction "COL_4") (pintype "passive"))
      (node (ref "DIR14") (pin "3") (pinfunction "3_3") (pintype "passive"))
      (node (ref "X4") (pin "1") (pinfunction "KL_1") (pintype "passive"))
    )
    (net (code "82") (name "P1") (class "Default")
      (node (ref "P1") (pin "2") (pinfunction "2_2") (pintype "passive"))
      (node (ref "X1") (pin "1") (pinfunction "KL_1") (pintype "passive"))
    )
    (net (code "83") (name "P2") (class "Default")
      (node (ref "P2") (pin "2") (pinfunction "2_2") (pintype "passive"))
      (node (ref "X1") (pin "4") (pinfunction "KL_4") (pintype "passive"))
    )
    (net (code "84") (name "P3") (class "Default")
      (node (ref "P3") (pin "2") (pinfunction "2_2") (pintype "passive"))
      (node (ref "X1") (pin "7") (pinfunction "KL_7") (pintype "passive"))
    )
    (net (code "85") (name "P4") (class "Default")
      (node (ref "P4") (pin "2") (pinfunction "2_2") (pintype "passive"))
      (node (ref "X1") (pin "10") (pinfunction "KL_10") (pintype "passive"))
    )
    (net (code "86") (name "P5") (class "Default")
      (node (ref "P5") (pin "2") (pinfunction "2_2") (pintype "passive"))
      (node (ref "X2") (pin "2") (pinfunction "KL_2") (pintype "passive"))
    )
    (net (code "87") (name "P6") (class "Default")
      (node (ref "P6") (pin "2") (pinfunction "2_2") (pintype "passive"))
      (node (ref "X2") (pin "5") (pinfunction "KL_5") (pintype "passive"))
    )
    (net (code "88") (name "P7") (class "Default")
      (node (ref "P7") (pin "2") (pinfunction "2_2") (pintype "passive"))
      (node (ref "X2") (pin "8") (pinfunction "KL_8") (pintype "passive"))
    )
    (net (code "89") (name "P8") (class "Default")
      (node (ref "P8") (pin "2") (pinfunction "2_2") (pintype "passive"))
      (node (ref "PAD1") (pin "1") (pinfunction "P_1") (pintype "passive"))
      (node (ref "PAD2") (pin "1") (pinfunction "P_1") (pintype "passive"))
      (node (ref "PAD3") (pin "1") (pinfunction "P_1") (pintype "passive"))
      (node (ref "PAD4") (pin "1") (pinfunction "P_1") (pintype "passive"))
      (node (ref "PAD5") (pin "1") (pinfunction "P_1") (pintype "passive"))
      (node (ref "PAD6") (pin "1") (pinfunction "P_1") (pintype "passive"))
      (node (ref "PAD7") (pin "1") (pinfunction "P_1") (pintype "passive"))
    )
    (net (code "90") (name "PE0") (class "Default")
      (node (ref "DIR8") (pin "1") (pinfunction "1_1") (pintype "passive"))
      (node (ref "I/O1") (pin "2") (pinfunction "2_2") (pintype "passive"))
    )
    (net (code "91") (name "PE1") (class "Default")
      (node (ref "DIR9") (pin "1") (pinfunction "1_1") (pintype "passive"))
      (node (ref "I/O1") (pin "1") (pinfunction "1_1") (pintype "passive"))
    )
    (net (code "92") (name "PE2") (class "Default")
      (node (ref "DIR10") (pin "1") (pinfunction "1_1") (pintype "passive"))
      (node (ref "I/O1") (pin "4") (pinfunction "4_4") (pintype "passive"))
    )
    (net (code "93") (name "PE3") (class "Default")
      (node (ref "DIR11") (pin "1") (pinfunction "1_1") (pintype "passive"))
      (node (ref "I/O1") (pin "3") (pinfunction "3_3") (pintype "passive"))
    )
    (net (code "94") (name "PE4") (class "Default")
      (node (ref "DIR12") (pin "1") (pinfunction "1_1") (pintype "passive"))
      (node (ref "I/O1") (pin "6") (pinfunction "6_6") (pintype "passive"))
    )
    (net (code "95") (name "PE5") (class "Default")
      (node (ref "DIR13") (pin "1") (pinfunction "1_1") (pintype "passive"))
      (node (ref "I/O1") (pin "5") (pinfunction "5_5") (pintype "passive"))
    )
    (net (code "96") (name "PE6") (class "Default")
      (node (ref "DIR14") (pin "1") (pinfunction "1_1") (pintype "passive"))
      (node (ref "I/O1") (pin "8") (pinfunction "8_8") (pintype "passive"))
    )
    (net (code "97") (name "PE7") (class "Default")
      (node (ref "DIR1") (pin "1") (pinfunction "1_1") (pintype "passive"))
      (node (ref "I/O1") (pin "7") (pinfunction "7_7") (pintype "passive"))
      (node (ref "IO1") (pin "1") (pinfunction "1_1") (pintype "passive"))
      (node (ref "R2") (pin "2") (pinfunction "2_2") (pintype "passive"))
    )
    (net (code "98") (name "PE8") (class "Default")
      (node (ref "DIR2") (pin "1") (pinfunction "1_1") (pintype "passive"))
      (node (ref "I/O1") (pin "10") (pinfunction "10_10") (pintype "passive"))
      (node (ref "IO2") (pin "1") (pinfunction "1_1") (pintype "passive"))
      (node (ref "R4") (pin "2") (pinfunction "2_2") (pintype "passive"))
    )
    (net (code "99") (name "PE9") (class "Default")
      (node (ref "DIR3") (pin "1") (pinfunction "1_1") (pintype "passive"))
      (node (ref "I/O1") (pin "9") (pinfunction "9_9") (pintype "passive"))
      (node (ref "IO3") (pin "1") (pinfunction "1_1") (pintype "passive"))
      (node (ref "R6") (pin "2") (pinfunction "2_2") (pintype "passive"))
    )
    (net (code "100") (name "PE10") (class "Default")
      (node (ref "DIR4") (pin "1") (pinfunction "1_1") (pintype "passive"))
      (node (ref "I/O1") (pin "12") (pinfunction "12_12") (pintype "passive"))
      (node (ref "IO4") (pin "1") (pinfunction "1_1") (pintype "passive"))
      (node (ref "R8") (pin "2") (pinfunction "2_2") (pintype "passive"))
    )
    (net (code "101") (name "PE11") (class "Default")
      (node (ref "DIR5") (pin "1") (pinfunction "1_1") (pintype "passive"))
      (node (ref "I/O1") (pin "11") (pinfunction "11_11") (pintype "passive"))
      (node (ref "IO5") (pin "1") (pinfunction "1_1") (pintype "passive"))
      (node (ref "R10") (pin "2") (pinfunction "2_2") (pintype "passive"))
    )
    (net (code "102") (name "PE12") (class "Default")
      (node (ref "DIR6") (pin "1") (pinfunction "1_1") (pintype "passive"))
      (node (ref "I/O1") (pin "14") (pinfunction "14_14") (pintype "passive"))
      (node (ref "IO6") (pin "1") (pinfunction "1_1") (pintype "passive"))
      (node (ref "R12") (pin "2") (pinfunction "2_2") (pintype "passive"))
    )
    (net (code "103") (name "PE13") (class "Default")
      (node (ref "DIR7") (pin "1") (pinfunction "1_1") (pintype "passive"))
      (node (ref "I/O1") (pin "13") (pinfunction "13_13") (pintype "passive"))
      (node (ref "IO7") (pin "1") (pinfunction "1_1") (pintype "passive"))
      (node (ref "R14") (pin "2") (pinfunction "2_2") (pintype "passive"))
    )
    (net (code "104") (name "VIN") (class "Default")
      (node (ref "I/O1") (pin "17") (pinfunction "17_17") (pintype "passive"))
      (node (ref "P1") (pin "1") (pinfunction "1_1") (pintype "passive"))
      (node (ref "P2") (pin "1") (pinfunction "1_1") (pintype "passive"))
      (node (ref "P3") (pin "1") (pinfunction "1_1") (pintype "passive"))
      (node (ref "P4") (pin "1") (pinfunction "1_1") (pintype "passive"))
      (node (ref "P5") (pin "1") (pinfunction "1_1") (pintype "passive"))
      (node (ref "P6") (pin "1") (pinfunction "1_1") (pintype "passive"))
      (node (ref "P7") (pin "1") (pinfunction "1_1") (pintype "passive"))
    )
    (net (code "105") (name "unconnected-(H1-MOUNT-PadB3,2)") (class "Default")
      (node (ref "H1") (pin "B3,2") (pinfunction "MOUNT_B3,2") (pintype "passive"))
    )
    (net (code "106") (name "unconnected-(H2-MOUNT-PadB3,2)") (class "Default")
      (node (ref "H2") (pin "B3,2") (pinfunction "MOUNT_B3,2") (pintype "passive"))
    )
    (net (code "107") (name "unconnected-(H3-MOUNT-PadB3,2)") (class "Default")
      (node (ref "H3") (pin "B3,2") (pinfunction "MOUNT_B3,2") (pintype "passive"))
    )
    (net (code "108") (name "unconnected-(H4-MOUNT-PadB3,2)") (class "Default")
      (node (ref "H4") (pin "B3,2") (pinfunction "MOUNT_B3,2") (pintype "passive"))
    )
  )
)
